# LEDBLINK.net
KiCad netlist of a schematic drawn in EAGLE
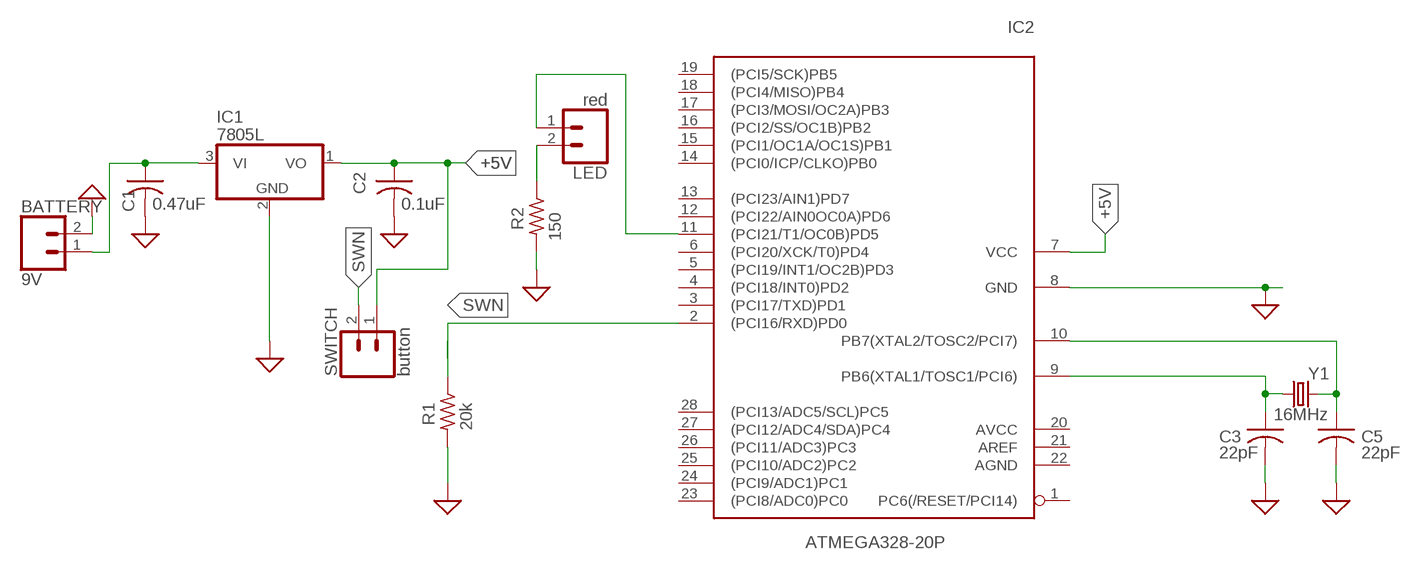
[diagram p0: schematic, sheet 1]

(export (version "E")
  (design (tool "Eeschema 10.0.6"))
  (components
    (comp (ref "BATTERY")
      (value "9V")
      (footprint "eagle-import:1X02")
      (libsource (lib "eagle-import") (part "CONN_02"))
    )
    (comp (ref "C1")
      (value "0.47uF")
      (footprint "eagle-import:C0805")
      (libsource (lib "eagle-import") (part "C-USC0805"))
    )
    (comp (ref "C2")
      (value "0.1uF")
      (footprint "eagle-import:C0805")
      (libsource (lib "eagle-import") (part "C-USC0805"))
    )
    (comp (ref "C3")
      (value "22pF")
      (footprint "eagle-import:C0805")
      (libsource (lib "eagle-import") (part "C-USC0805"))
    )
    (comp (ref "C5")
      (value "22pF")
      (footprint "eagle-import:C0805")
      (libsource (lib "eagle-import") (part "C-USC0805"))
    )
    (comp (ref "IC1")
      (value "7805L")
      (footprint "eagle-import:TO92")
      (libsource (lib "eagle-import") (part "78L05"))
    )
    (comp (ref "IC2")
      (value "ATMEGA328-20P")
      (footprint "eagle-import:DIL28-3")
      (libsource (lib "eagle-import") (part "ATMEGA328P-20"))
    )
    (comp (ref "LED")
      (value "red")
      (footprint "eagle-import:1X02")
      (libsource (lib "eagle-import") (part "CONN_02"))
    )
    (comp (ref "R1")
      (value "20k")
      (footprint "eagle-import:R0805")
      (libsource (lib "eagle-import") (part "R-US_R0805"))
    )
    (comp (ref "R2")
      (value "150")
      (footprint "eagle-import:R0805")
      (libsource (lib "eagle-import") (part "R-US_R0805"))
    )
    (comp (ref "SWITCH")
      (value "button")
      (footprint "eagle-import:1X02")
      (libsource (lib "eagle-import") (part "CONN_02"))
    )
    (comp (ref "Y1")
      (value "16MHz")
      (footprint "eagle-import:HC49US")
      (libsource (lib "eagle-import") (part "CRYSTAL-16MHZPTH-HC49US"))
    )
  )
  (nets
    (net (code "1") (name "+5V") (class "Default")
      (node (ref "C2") (pin "1") (pinfunction "1_1") (pintype "passive"))
      (node (ref "IC1") (pin "1") (pinfunction "VO_1") (pintype "passive"))
      (node (ref "IC2") (pin "7") (pinfunction "VCC_7") (pintype "bidirectional"))
      (node (ref "SWITCH") (pin "1") (pinfunction "1_1") (pintype "passive"))
    )
    (net (code "2") (name "Net-(IC1-VI)") (class "Default")
      (node (ref "BATTERY") (pin "1") (pinfunction "1_1") (pintype "passive"))
      (node (ref "C1") (pin "1") (pinfunction "1_1") (pintype "passive"))
      (node (ref "IC1") (pin "3") (pinfunction "VI_3") (pintype "input"))
    )
    (net (code "3") (name "Net-(IC2-(PCI21{slash}T1{slash}OC0B)PD5)") (class "Default")
      (node (ref "IC2") (pin "11") (pinfunction "(PCI21/T1/OC0B)PD5_11") (pintype "bidirectional"))
      (node (ref "LED") (pin "1") (pinfunction "1_1") (pintype "passive"))
    )
    (net (code "4") (name "Net-(IC2-PB6(XTAL1{slash}TOSC1{slash}PCI6))") (class "Default")
      (node (ref "C3") (pin "1") (pinfunction "1_1") (pintype "passive"))
      (node (ref "IC2") (pin "9") (pinfunction "PB6(XTAL1/TOSC1/PCI6)_9") (pintype "bidirectional"))
      (node (ref "Y1") (pin "1") (pinfunction "1_1") (pintype "passive"))
    )
    (net (code "5") (name "Net-(IC2-PB7(XTAL2{slash}TOSC2{slash}PCI7))") (class "Default")
      (node (ref "C5") (pin "1") (pinfunction "1_1") (pintype "passive"))
      (node (ref "IC2") (pin "10") (pinfunction "PB7(XTAL2/TOSC2/PCI7)_10") (pintype "bidirectional"))
      (node (ref "Y1") (pin "2") (pinfunction "2_2") (pintype "passive"))
    )
    (net (code "6") (name "Net-(LED-Pad2)") (class "Default")
      (node (ref "LED") (pin "2") (pinfunction "2_2") (pintype "passive"))
      (node (ref "R2") (pin "1") (pinfunction "1_1") (pintype "passive"))
    )
    (net (code "7") (name "SUP") (class "Default")
      (node (ref "BATTERY") (pin "2") (pinfunction "2_2") (pintype "passive"))
      (node (ref "C1") (pin "2") (pinfunction "2_2") (pintype "passive"))
      (node (ref "C2") (pin "2") (pinfunction "2_2") (pintype "passive"))
      (node (ref "C3") (pin "2") (pinfunction "2_2") (pintype "passive"))
      (node (ref "C5") (pin "2") (pinfunction "2_2") (pintype "passive"))
      (node (ref "IC1") (pin "2") (pinfunction "GND_2") (pintype "passive"))
      (node (ref "IC2") (pin "8") (pinfunction "GND_8") (pintype "bidirectional"))
      (node (ref "R1") (pin "2") (pinfunction "2_2") (pintype "passive"))
      (node (ref "R2") (pin "2") (pinfunction "2_2") (pintype "passive"))
    )
    (net (code "8") (name "SWN") (class "Default")
      (node (ref "IC2") (pin "2") (pinfunction "(PCI16/RXD)PD0_2") (pintype "bidirectional"))
      (node (ref "R1") (pin "1") (pinfunction "1_1") (pintype "passive"))
      (node (ref "SWITCH") (pin "2") (pinfunction "2_2") (pintype "passive"))
    )
    (net (code "9") (name "unconnected-(IC2-(PCI0{slash}ICP{slash}CLKO)PB0-Pad14)") (class "Default")
      (node (ref "IC2") (pin "14") (pinfunction "(PCI0/ICP/CLKO)PB0_14") (pintype "bidirectional"))
    )
    (net (code "10") (name "unconnected-(IC2-(PCI1{slash}OC1A{slash}OC1S)PB1-Pad15)") (class "Default")
      (node (ref "IC2") (pin "15") (pinfunction "(PCI1/OC1A/OC1S)PB1_15") (pintype "bidirectional"))
    )
    (net (code "11") (name "unconnected-(IC2-(PCI2{slash}SS{slash}OC1B)PB2-Pad16)") (class "Default")
      (node (ref "IC2") (pin "16") (pinfunction "(PCI2/SS/OC1B)PB2_16") (pintype "bidirectional"))
    )
    (net (code "12") (name "unconnected-(IC2-(PCI3{slash}MOSI{slash}OC2A)PB3-Pad17)") (class "Default")
      (node (ref "IC2") (pin "17") (pinfunction "(PCI3/MOSI/OC2A)PB3_17") (pintype "bidirectional"))
    )
    (net (code "13") (name "unconnected-(IC2-(PCI4{slash}MISO)PB4-Pad18)") (class "Default")
      (node (ref "IC2") (pin "18") (pinfunction "(PCI4/MISO)PB4_18") (pintype "bidirectional"))
    )
    (net (code "14") (name "unconnected-(IC2-(PCI5{slash}SCK)PB5-Pad19)") (class "Default")
      (node (ref "IC2") (pin "19") (pinfunction "(PCI5/SCK)PB5_19") (pintype "bidirectional"))
    )
    (net (code "15") (name "unconnected-(IC2-(PCI8{slash}ADC0)PC0-Pad23)") (class "Default")
      (node (ref "IC2") (pin "23") (pinfunction "(PCI8/ADC0)PC0_23") (pintype "bidirectional"))
    )
    (net (code "16") (name "unconnected-(IC2-(PCI9{slash}ADC1)PC1-Pad24)") (class "Default")
      (node (ref "IC2") (pin "24") (pinfunction "(PCI9/ADC1)PC1_24") (pintype "bidirectional"))
    )
    (net (code "17") (name "unconnected-(IC2-(PCI10{slash}ADC2)PC2-Pad25)") (class "Default")
      (node (ref "IC2") (pin "25") (pinfunction "(PCI10/ADC2)PC2_25") (pintype "bidirectional"))
    )
    (net (code "18") (name "unconnected-(IC2-(PCI11{slash}ADC3)PC3-Pad26)") (class "Default")
      (node (ref "IC2") (pin "26") (pinfunction "(PCI11/ADC3)PC3_26") (pintype "bidirectional"))
    )
    (net (code "19") (name "unconnected-(IC2-(PCI12{slash}ADC4{slash}SDA)PC4-Pad27)") (class "Default")
      (node (ref "IC2") (pin "27") (pinfunction "(PCI12/ADC4/SDA)PC4_27") (pintype "bidirectional"))
    )
    (net (code "20") (name "unconnected-(IC2-(PCI13{slash}ADC5{slash}SCL)PC5-Pad28)") (class "Default")
      (node (ref "IC2") (pin "28") (pinfunction "(PCI13/ADC5/SCL)PC5_28") (pintype "bidirectional"))
    )
    (net (code "21") (name "unconnected-(IC2-(PCI17{slash}TXD)PD1-Pad3)") (class "Default")
      (node (ref "IC2") (pin "3") (pinfunction "(PCI17/TXD)PD1_3") (pintype "bidirectional"))
    )
    (net (code "22") (name "unconnected-(IC2-(PCI18{slash}INT0)PD2-Pad4)") (class "Default")
      (node (ref "IC2") (pin "4") (pinfunction "(PCI18/INT0)PD2_4") (pintype "bidirectional"))
    )
    (net (code "23") (name "unconnected-(IC2-(PCI19{slash}INT1{slash}OC2B)PD3-Pad5)") (class "Default")
      (node (ref "IC2") (pin "5") (pinfunction "(PCI19/INT1/OC2B)PD3_5") (pintype "bidirectional"))
    )
    (net (code "24") (name "unconnected-(IC2-(PCI20{slash}XCK{slash}T0)PD4-Pad6)") (class "Default")
      (node (ref "IC2") (pin "6") (pinfunction "(PCI20/XCK/T0)PD4_6") (pintype "bidirectional"))
    )
    (net (code "25") (name "unconnected-(IC2-(PCI22{slash}AIN0OC0A)PD6-Pad12)") (class "Default")
      (node (ref "IC2") (pin "12") (pinfunction "(PCI22/AIN0OC0A)PD6_12") (pintype "bidirectional"))
    )
    (net (code "26") (name "unconnected-(IC2-(PCI23{slash}AIN1)PD7-Pad13)") (class "Default")
      (node (ref "IC2") (pin "13") (pinfunction "(PCI23/AIN1)PD7_13") (pintype "bidirectional"))
    )
    (net (code "27") (name "unconnected-(IC2-AGND-Pad22)") (class "Default")
      (node (ref "IC2") (pin "22") (pinfunction "AGND_22") (pintype "bidirectional"))
    )
    (net (code "28") (name "unconnected-(IC2-AREF-Pad21)") (class "Default")
      (node (ref "IC2") (pin "21") (pinfunction "AREF_21") (pintype "bidirectional"))
    )
    (net (code "29") (name "unconnected-(IC2-AVCC-Pad20)") (class "Default")
      (node (ref "IC2") (pin "20") (pinfunction "AVCC_20") (pintype "bidirectional"))
    )
    (net (code "30") (name "unconnected-(IC2-PC6({slash}RESET{slash}PCI14)-Pad1)") (class "Default")
      (node (ref "IC2") (pin "1") (pinfunction "PC6(/RESET/PCI14)_1") (pintype "bidirectional"))
    )
  )
)
